# wifi-hat.net
KiCad netlist of a schematic drawn in EAGLE
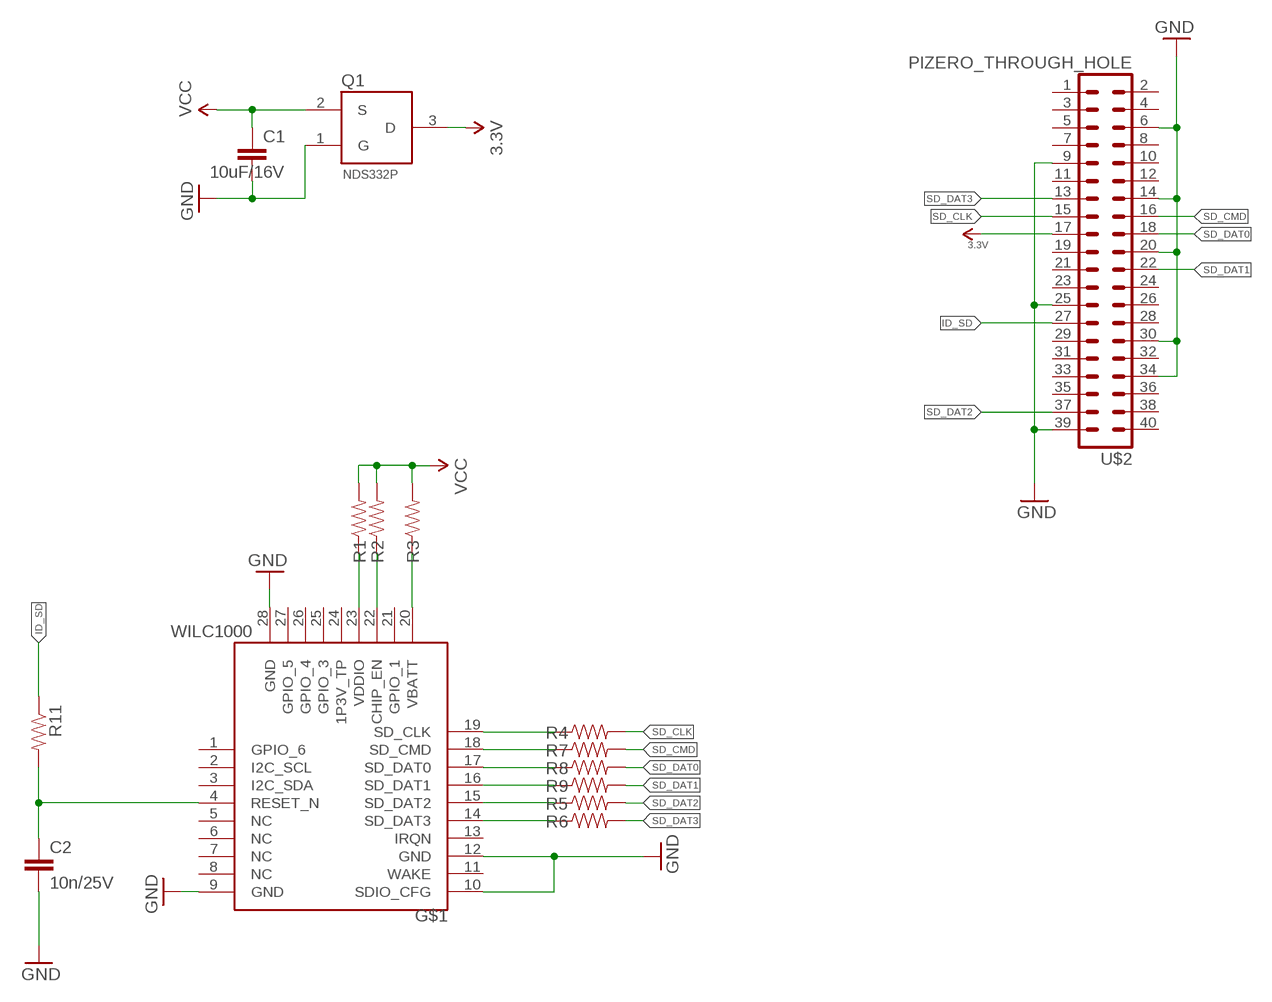
[diagram p0: schematic, sheet 1]

(export (version "E")
  (design (tool "Eeschema 10.0.6"))
  (components
    (comp (ref "C1")
      (value "10uF/16V")
      (footprint "eagle-import:C0603K")
      (libsource (lib "eagle-import") (part "C-EUC0603K"))
    )
    (comp (ref "C2")
      (value "10n/25V")
      (footprint "eagle-import:C0603K")
      (libsource (lib "eagle-import") (part "C-EUC0603K"))
    )
    (comp (ref "Q1")
      (value "NDS332P")
      (footprint "eagle-import:SOT23")
      (libsource (lib "eagle-import") (part "NDS332P-SAG"))
    )
    (comp (ref "R1")
      (value "0 Ohm")
      (footprint "eagle-import:0603-RES")
      (libsource (lib "eagle-import") (part "RESISTOR0603-RES"))
    )
    (comp (ref "R2")
      (value "1M Ohm")
      (footprint "eagle-import:0603-RES")
      (libsource (lib "eagle-import") (part "RESISTOR0603-RES"))
    )
    (comp (ref "R3")
      (value "0 Ohm")
      (footprint "eagle-import:0603-RES")
      (libsource (lib "eagle-import") (part "RESISTOR0603-RES"))
    )
    (comp (ref "R4")
      (value "75 Ohm")
      (footprint "eagle-import:0603-RES")
      (libsource (lib "eagle-import") (part "RESISTOR0603-RES"))
    )
    (comp (ref "R5")
      (value "75 Ohm")
      (footprint "eagle-import:0603-RES")
      (libsource (lib "eagle-import") (part "RESISTOR0603-RES"))
    )
    (comp (ref "R6")
      (value "75 Ohm")
      (footprint "eagle-import:0603-RES")
      (libsource (lib "eagle-import") (part "RESISTOR0603-RES"))
    )
    (comp (ref "R7")
      (value "75 Ohm")
      (footprint "eagle-import:0603-RES")
      (libsource (lib "eagle-import") (part "RESISTOR0603-RES"))
    )
    (comp (ref "R8")
      (value "75 Ohm")
      (footprint "eagle-import:0603-RES")
      (libsource (lib "eagle-import") (part "RESISTOR0603-RES"))
    )
    (comp (ref "R9")
      (value "75 Ohm")
      (footprint "eagle-import:0603-RES")
      (libsource (lib "eagle-import") (part "RESISTOR0603-RES"))
    )
    (comp (ref "R11")
      (value "1M Ohm")
      (footprint "eagle-import:0603-RES")
      (libsource (lib "eagle-import") (part "RESISTOR0603-RES"))
    )
    (comp (ref "U$2")
      (value "PIZERO_THROUGH_HOLE")
      (footprint "eagle-import:PIZERO_THOUGH_HOLE")
      (libsource (lib "eagle-import") (part "PIZERO_THROUGH_HOLE"))
    )
    (comp (ref "WI_SOC")
      (value "WILC1000")
      (footprint "eagle-import:ATWILC1000-MR110PA")
      (libsource (lib "eagle-import") (part "ATWILC1000-MR110PA"))
    )
  )
  (nets
    (net (code "1") (name "/1P3V_TP") (class "Default")
      (node (ref "WI_SOC") (pin "24") (pinfunction "1P3V_TP_24") (pintype "power_in"))
    )
    (net (code "2") (name "3.3V") (class "Default")
      (node (ref "Q1") (pin "3") (pinfunction "D_3") (pintype "output"))
      (node (ref "U$2") (pin "17") (pinfunction "17_17") (pintype "passive"))
    )
    (net (code "3") (name "GND") (class "Default")
      (node (ref "C1") (pin "2") (pinfunction "2_2") (pintype "passive"))
      (node (ref "C2") (pin "2") (pinfunction "2_2") (pintype "passive"))
      (node (ref "Q1") (pin "1") (pinfunction "G_1") (pintype "power_in"))
      (node (ref "U$2") (pin "14") (pinfunction "14_14") (pintype "passive"))
      (node (ref "U$2") (pin "20") (pinfunction "20_20") (pintype "passive"))
      (node (ref "U$2") (pin "25") (pinfunction "25_25") (pintype "passive"))
      (node (ref "U$2") (pin "30") (pinfunction "30_30") (pintype "passive"))
      (node (ref "U$2") (pin "34") (pinfunction "34_34") (pintype "passive"))
      (node (ref "U$2") (pin "39") (pinfunction "39_39") (pintype "passive"))
      (node (ref "U$2") (pin "6") (pinfunction "6_6") (pintype "passive"))
      (node (ref "U$2") (pin "9") (pinfunction "9_9") (pintype "passive"))
      (node (ref "WI_SOC") (pin "10") (pinfunction "SDIO_CFG_10") (pintype "input"))
      (node (ref "WI_SOC") (pin "12") (pinfunction "GND_12") (pintype "power_in"))
      (node (ref "WI_SOC") (pin "28") (pinfunction "GND_28") (pintype "power_in"))
      (node (ref "WI_SOC") (pin "9") (pinfunction "GND_9") (pintype "power_in"))
    )
    (net (code "4") (name "ID_SD") (class "Default")
      (node (ref "R11") (pin "1") (pinfunction "1_1") (pintype "passive"))
      (node (ref "U$2") (pin "27") (pinfunction "27_27") (pintype "passive"))
    )
    (net (code "5") (name "Net-(WI_SOC-CHIP_EN)") (class "Default")
      (node (ref "R2") (pin "1") (pinfunction "1_1") (pintype "passive"))
      (node (ref "WI_SOC") (pin "22") (pinfunction "CHIP_EN_22") (pintype "input"))
    )
    (net (code "6") (name "Net-(WI_SOC-RESET_N)") (class "Default")
      (node (ref "C2") (pin "1") (pinfunction "1_1") (pintype "passive"))
      (node (ref "R11") (pin "2") (pinfunction "2_2") (pintype "passive"))
      (node (ref "WI_SOC") (pin "4") (pinfunction "RESET_N_4") (pintype "input"))
    )
    (net (code "7") (name "Net-(WI_SOC-SD_CLK)") (class "Default")
      (node (ref "R4") (pin "1") (pinfunction "1_1") (pintype "passive"))
      (node (ref "WI_SOC") (pin "19") (pinfunction "SD_CLK_19") (pintype "input"))
    )
    (net (code "8") (name "Net-(WI_SOC-SD_CMD)") (class "Default")
      (node (ref "R7") (pin "1") (pinfunction "1_1") (pintype "passive"))
      (node (ref "WI_SOC") (pin "18") (pinfunction "SD_CMD_18") (pintype "bidirectional"))
    )
    (net (code "9") (name "Net-(WI_SOC-SD_DAT0)") (class "Default")
      (node (ref "R8") (pin "1") (pinfunction "1_1") (pintype "passive"))
      (node (ref "WI_SOC") (pin "17") (pinfunction "SD_DAT0_17") (pintype "bidirectional"))
    )
    (net (code "10") (name "Net-(WI_SOC-SD_DAT1)") (class "Default")
      (node (ref "R9") (pin "1") (pinfunction "1_1") (pintype "passive"))
      (node (ref "WI_SOC") (pin "16") (pinfunction "SD_DAT1_16") (pintype "bidirectional"))
    )
    (net (code "11") (name "Net-(WI_SOC-SD_DAT2)") (class "Default")
      (node (ref "R5") (pin "1") (pinfunction "1_1") (pintype "passive"))
      (node (ref "WI_SOC") (pin "15") (pinfunction "SD_DAT2_15") (pintype "bidirectional"))
    )
    (net (code "12") (name "Net-(WI_SOC-SD_DAT3)") (class "Default")
      (node (ref "R6") (pin "1") (pinfunction "1_1") (pintype "passive"))
      (node (ref "WI_SOC") (pin "14") (pinfunction "SD_DAT3_14") (pintype "bidirectional"))
    )
    (net (code "13") (name "Net-(WI_SOC-VBATT)") (class "Default")
      (node (ref "R3") (pin "1") (pinfunction "1_1") (pintype "passive"))
      (node (ref "WI_SOC") (pin "20") (pinfunction "VBATT_20") (pintype "power_in"))
    )
    (net (code "14") (name "Net-(WI_SOC-VDDIO)") (class "Default")
      (node (ref "R1") (pin "1") (pinfunction "1_1") (pintype "passive"))
      (node (ref "WI_SOC") (pin "23") (pinfunction "VDDIO_23") (pintype "power_in"))
    )
    (net (code "15") (name "SD_CLK") (class "Default")
      (node (ref "R4") (pin "2") (pinfunction "2_2") (pintype "passive"))
      (node (ref "U$2") (pin "15") (pinfunction "15_15") (pintype "passive"))
    )
    (net (code "16") (name "SD_CMD") (class "Default")
      (node (ref "R7") (pin "2") (pinfunction "2_2") (pintype "passive"))
      (node (ref "U$2") (pin "16") (pinfunction "16_16") (pintype "passive"))
    )
    (net (code "17") (name "SD_DAT0") (class "Default")
      (node (ref "R8") (pin "2") (pinfunction "2_2") (pintype "passive"))
      (node (ref "U$2") (pin "18") (pinfunction "18_18") (pintype "passive"))
    )
    (net (code "18") (name "SD_DAT1") (class "Default")
      (node (ref "R9") (pin "2") (pinfunction "2_2") (pintype "passive"))
      (node (ref "U$2") (pin "22") (pinfunction "22_22") (pintype "passive"))
    )
    (net (code "19") (name "SD_DAT2") (class "Default")
      (node (ref "R5") (pin "2") (pinfunction "2_2") (pintype "passive"))
      (node (ref "U$2") (pin "37") (pinfunction "37_37") (pintype "passive"))
    )
    (net (code "20") (name "SD_DAT3") (class "Default")
      (node (ref "R6") (pin "2") (pinfunction "2_2") (pintype "passive"))
      (node (ref "U$2") (pin "13") (pinfunction "13_13") (pintype "passive"))
    )
    (net (code "21") (name "VCC") (class "Default")
      (node (ref "C1") (pin "1") (pinfunction "1_1") (pintype "passive"))
      (node (ref "Q1") (pin "2") (pinfunction "S_2") (pintype "power_in"))
      (node (ref "R1") (pin "2") (pinfunction "2_2") (pintype "passive"))
      (node (ref "R2") (pin "2") (pinfunction "2_2") (pintype "passive"))
      (node (ref "R3") (pin "2") (pinfunction "2_2") (pintype "passive"))
    )
    (net (code "22") (name "unconnected-(U$2-Pad1)") (class "Default")
      (node (ref "U$2") (pin "1") (pinfunction "1_1") (pintype "passive"))
    )
    (net (code "23") (name "unconnected-(U$2-Pad2)") (class "Default")
      (node (ref "U$2") (pin "2") (pinfunction "2_2") (pintype "passive"))
    )
    (net (code "24") (name "unconnected-(U$2-Pad3)") (class "Default")
      (node (ref "U$2") (pin "3") (pinfunction "3_3") (pintype "passive"))
    )
    (net (code "25") (name "unconnected-(U$2-Pad4)") (class "Default")
      (node (ref "U$2") (pin "4") (pinfunction "4_4") (pintype "passive"))
    )
    (net (code "26") (name "unconnected-(U$2-Pad5)") (class "Default")
      (node (ref "U$2") (pin "5") (pinfunction "5_5") (pintype "passive"))
    )
    (net (code "27") (name "unconnected-(U$2-Pad7)") (class "Default")
      (node (ref "U$2") (pin "7") (pinfunction "7_7") (pintype "passive"))
    )
    (net (code "28") (name "unconnected-(U$2-Pad8)") (class "Default")
      (node (ref "U$2") (pin "8") (pinfunction "8_8") (pintype "passive"))
    )
    (net (code "29") (name "unconnected-(U$2-Pad10)") (class "Default")
      (node (ref "U$2") (pin "10") (pinfunction "10_10") (pintype "passive"))
    )
    (net (code "30") (name "unconnected-(U$2-Pad11)") (class "Default")
      (node (ref "U$2") (pin "11") (pinfunction "11_11") (pintype "passive"))
    )
    (net (code "31") (name "unconnected-(U$2-Pad12)") (class "Default")
      (node (ref "U$2") (pin "12") (pinfunction "12_12") (pintype "passive"))
    )
    (net (code "32") (name "unconnected-(U$2-Pad19)") (class "Default")
      (node (ref "U$2") (pin "19") (pinfunction "19_19") (pintype "passive"))
    )
    (net (code "33") (name "unconnected-(U$2-Pad21)") (class "Default")
      (node (ref "U$2") (pin "21") (pinfunction "21_21") (pintype "passive"))
    )
    (net (code "34") (name "unconnected-(U$2-Pad23)") (class "Default")
      (node (ref "U$2") (pin "23") (pinfunction "23_23") (pintype "passive"))
    )
    (net (code "35") (name "unconnected-(U$2-Pad24)") (class "Default")
      (node (ref "U$2") (pin "24") (pinfunction "24_24") (pintype "passive"))
    )
    (net (code "36") (name "unconnected-(U$2-Pad26)") (class "Default")
      (node (ref "U$2") (pin "26") (pinfunction "26_26") (pintype "passive"))
    )
    (net (code "37") (name "unconnected-(U$2-Pad28)") (class "Default")
      (node (ref "U$2") (pin "28") (pinfunction "28_28") (pintype "passive"))
    )
    (net (code "38") (name "unconnected-(U$2-Pad29)") (class "Default")
      (node (ref "U$2") (pin "29") (pinfunction "29_29") (pintype "passive"))
    )
    (net (code "39") (name "unconnected-(U$2-Pad31)") (class "Default")
      (node (ref "U$2") (pin "31") (pinfunction "31_31") (pintype "passive"))
    )
    (net (code "40") (name "unconnected-(U$2-Pad32)") (class "Default")
      (node (ref "U$2") (pin "32") (pinfunction "32_32") (pintype "passive"))
    )
    (net (code "41") (name "unconnected-(U$2-Pad33)") (class "Default")
      (node (ref "U$2") (pin "33") (pinfunction "33_33") (pintype "passive"))
    )
    (net (code "42") (name "unconnected-(U$2-Pad35)") (class "Default")
      (node (ref "U$2") (pin "35") (pinfunction "35_35") (pintype "passive"))
    )
    (net (code "43") (name "unconnected-(U$2-Pad36)") (class "Default")
      (node (ref "U$2") (pin "36") (pinfunction "36_36") (pintype "passive"))
    )
    (net (code "44") (name "unconnected-(U$2-Pad38)") (class "Default")
      (node (ref "U$2") (pin "38") (pinfunction "38_38") (pintype "passive"))
    )
    (net (code "45") (name "unconnected-(U$2-Pad40)") (class "Default")
      (node (ref "U$2") (pin "40") (pinfunction "40_40") (pintype "passive"))
    )
    (net (code "46") (name "unconnected-(WI_SOC-GPIO_1-Pad21)") (class "Default")
      (node (ref "WI_SOC") (pin "21") (pinfunction "GPIO_1_21") (pintype "bidirectional"))
    )
    (net (code "47") (name "unconnected-(WI_SOC-GPIO_3-Pad25)") (class "Default")
      (node (ref "WI_SOC") (pin "25") (pinfunction "GPIO_3_25") (pintype "bidirectional"))
    )
    (net (code "48") (name "unconnected-(WI_SOC-GPIO_4-Pad26)") (class "Default")
      (node (ref "WI_SOC") (pin "26") (pinfunction "GPIO_4_26") (pintype "bidirectional"))
    )
    (net (code "49") (name "unconnected-(WI_SOC-GPIO_5-Pad27)") (class "Default")
      (node (ref "WI_SOC") (pin "27") (pinfunction "GPIO_5_27") (pintype "bidirectional"))
    )
    (net (code "50") (name "unconnected-(WI_SOC-GPIO_6-Pad1)") (class "Default")
      (node (ref "WI_SOC") (pin "1") (pinfunction "GPIO_6_1") (pintype "bidirectional"))
    )
    (net (code "51") (name "unconnected-(WI_SOC-I2C_SCL-Pad2)") (class "Default")
      (node (ref "WI_SOC") (pin "2") (pinfunction "I2C_SCL_2") (pintype "bidirectional"))
    )
    (net (code "52") (name "unconnected-(WI_SOC-I2C_SDA-Pad3)") (class "Default")
      (node (ref "WI_SOC") (pin "3") (pinfunction "I2C_SDA_3") (pintype "bidirectional"))
    )
    (net (code "53") (name "unconnected-(WI_SOC-IRQN-Pad13)") (class "Default")
      (node (ref "WI_SOC") (pin "13") (pinfunction "IRQN_13") (pintype "output"))
    )
    (net (code "54") (name "unconnected-(WI_SOC-NC-Pad5)") (class "Default")
      (node (ref "WI_SOC") (pin "5") (pinfunction "NC_5") (pintype "no_connect"))
    )
    (net (code "55") (name "unconnected-(WI_SOC-NC-Pad6)") (class "Default")
      (node (ref "WI_SOC") (pin "6") (pinfunction "NC_6") (pintype "no_connect"))
    )
    (net (code "56") (name "unconnected-(WI_SOC-NC-Pad7)") (class "Default")
      (node (ref "WI_SOC") (pin "7") (pinfunction "NC_7") (pintype "no_connect"))
    )
    (net (code "57") (name "unconnected-(WI_SOC-NC-Pad8)") (class "Default")
      (node (ref "WI_SOC") (pin "8") (pinfunction "NC_8") (pintype "no_connect"))
    )
    (net (code "58") (name "unconnected-(WI_SOC-WAKE-Pad11)") (class "Default")
      (node (ref "WI_SOC") (pin "11") (pinfunction "WAKE_11") (pintype "input"))
    )
  )
)
